# main.net
KiCad netlist of a schematic drawn in EAGLE
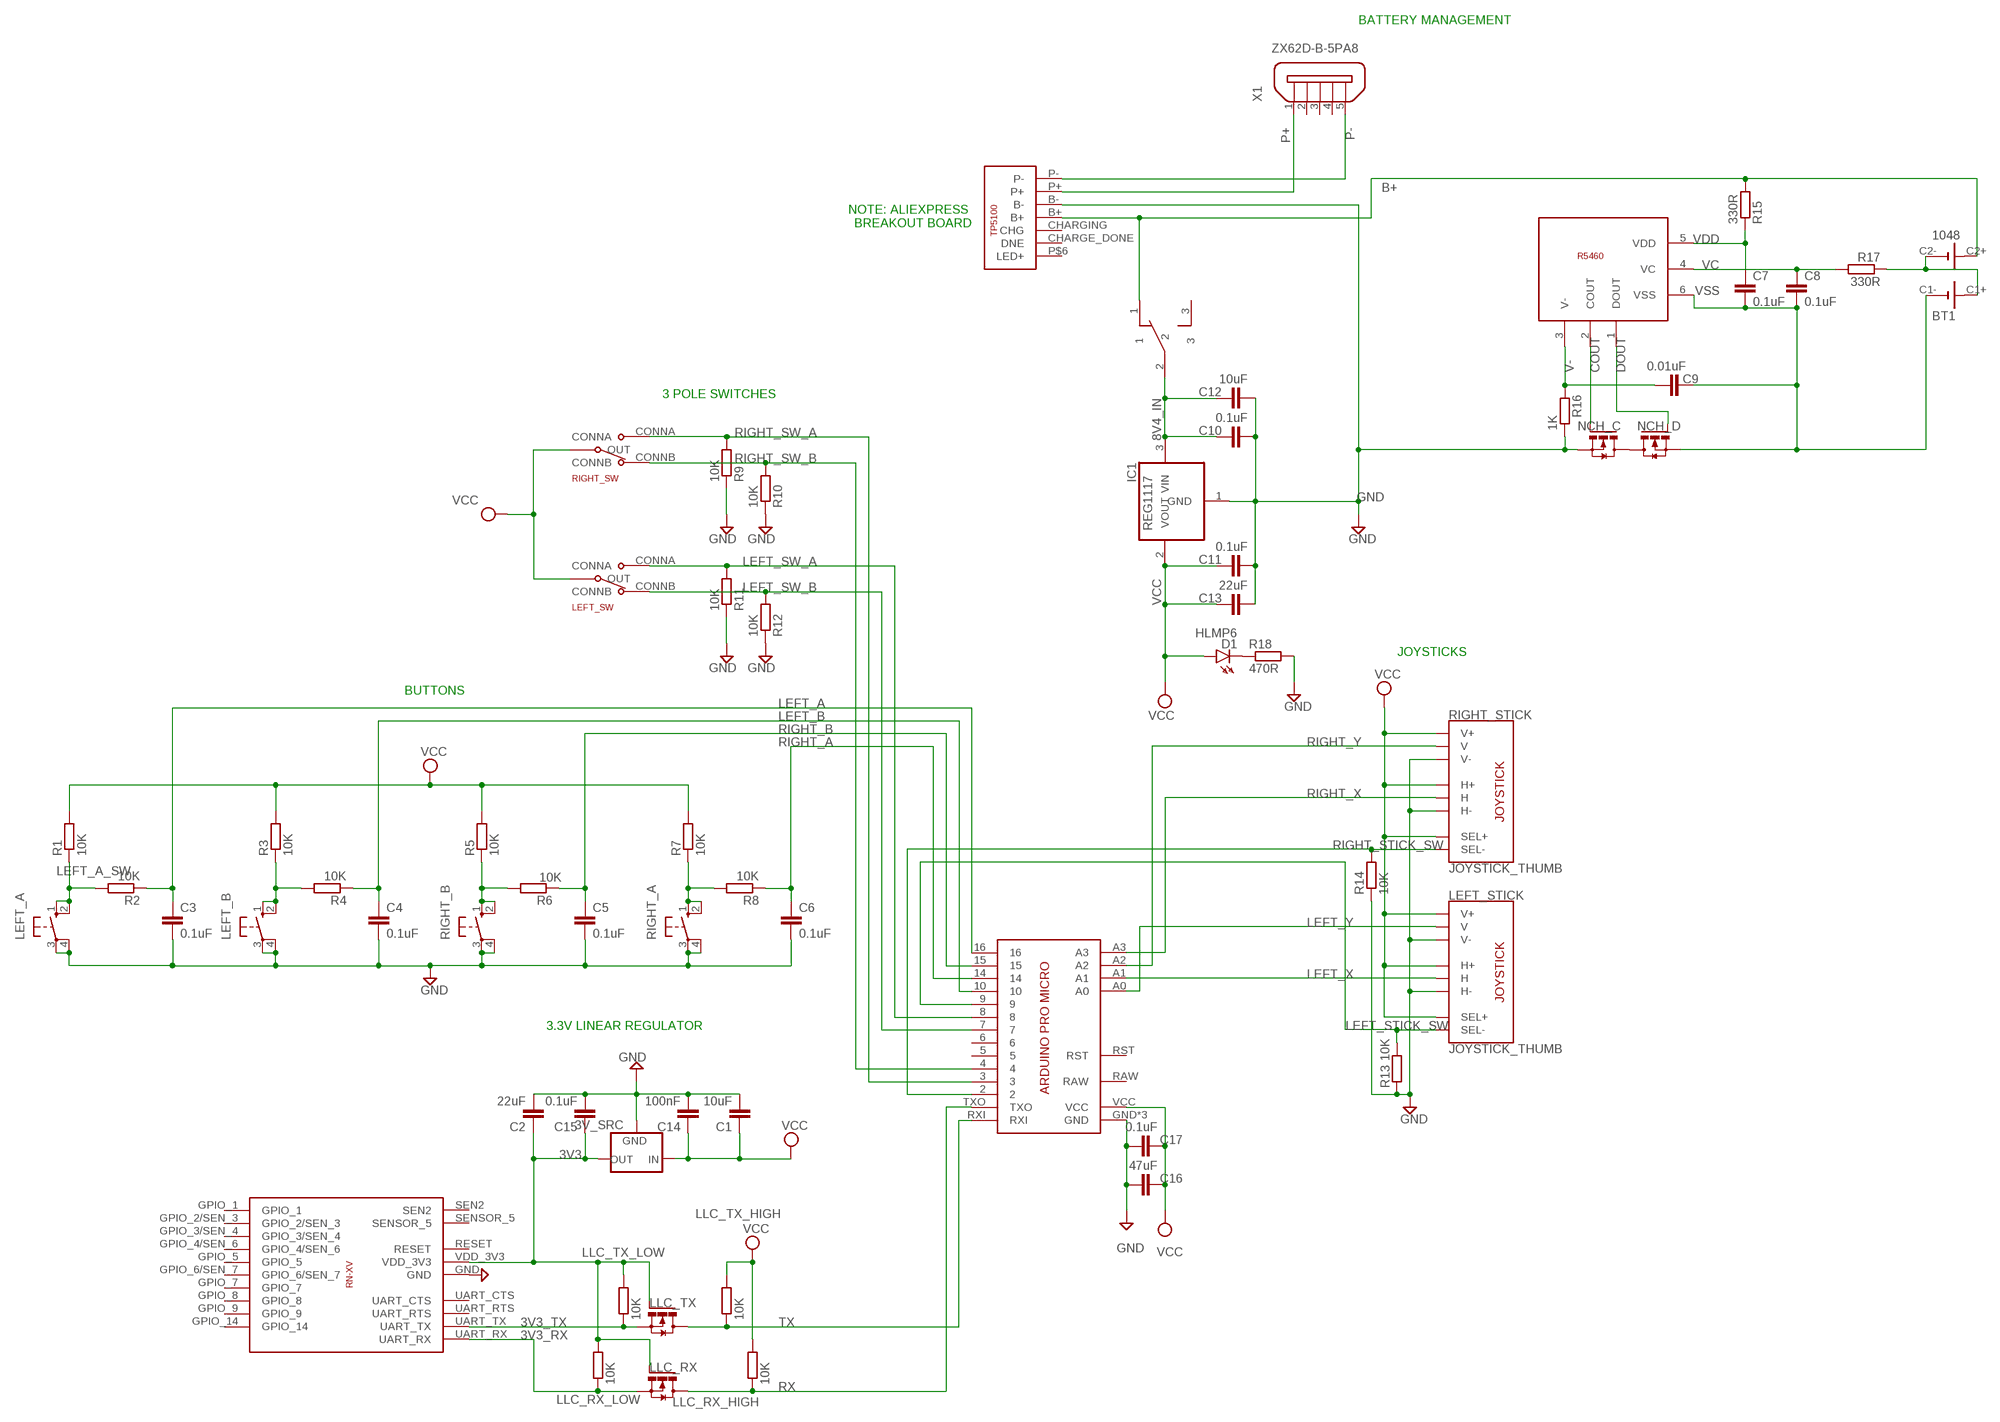
[diagram p0: schematic, sheet 1]

(export (version "E")
  (design (tool "Eeschema 10.0.6"))
  (components
    (comp (ref "3V_SRC")
      (value "V_REG_LD1117VXXLD1117-SMD")
      (footprint "eagle-import:SOT223")
      (libsource (lib "eagle-import") (part "V_REG_LD1117VXXLD1117-SMD"))
    )
    (comp (ref "BT1")
      (value "1048")
      (footprint "eagle-import:BAT_1048")
      (fields (field (name "MF") "Adafruit Industries"))
      (libsource (lib "eagle-import") (part "1048"))
    )
    (comp (ref "C1")
      (value "10uF")
      (footprint "eagle-import:C0805")
      (libsource (lib "eagle-import") (part "C-EUC0805"))
    )
    (comp (ref "C2")
      (value "22uF")
      (footprint "eagle-import:C0805")
      (libsource (lib "eagle-import") (part "C-EUC0805"))
    )
    (comp (ref "C3")
      (value "0.1uF")
      (footprint "eagle-import:0603")
      (libsource (lib "eagle-import") (part "0.1UF-0603-25V-5%"))
    )
    (comp (ref "C4")
      (value "0.1uF")
      (footprint "eagle-import:0603")
      (libsource (lib "eagle-import") (part "0.1UF-0603-25V-5%"))
    )
    (comp (ref "C5")
      (value "0.1uF")
      (footprint "eagle-import:0603")
      (libsource (lib "eagle-import") (part "0.1UF-0603-25V-5%"))
    )
    (comp (ref "C6")
      (value "0.1uF")
      (footprint "eagle-import:0603")
      (libsource (lib "eagle-import") (part "0.1UF-0603-25V-5%"))
    )
    (comp (ref "C7")
      (value "0.1uF")
      (footprint "eagle-import:0603")
      (libsource (lib "eagle-import") (part "0.1UF-0603-25V-(+80/-20%)"))
    )
    (comp (ref "C8")
      (value "0.1uF")
      (footprint "eagle-import:0603")
      (libsource (lib "eagle-import") (part "0.1UF-0603-25V-(+80/-20%)"))
    )
    (comp (ref "C9")
      (value "0.01uF")
      (footprint "eagle-import:0603")
      (libsource (lib "eagle-import") (part "0.1UF-0603-25V-(+80/-20%)"))
    )
    (comp (ref "C10")
      (value "0.1uF")
      (footprint "eagle-import:C0805")
      (libsource (lib "eagle-import") (part "C-EUC0805"))
    )
    (comp (ref "C11")
      (value "0.1uF")
      (footprint "eagle-import:C0805")
      (libsource (lib "eagle-import") (part "C-EUC0805"))
    )
    (comp (ref "C12")
      (value "10uF")
      (footprint "eagle-import:C0805")
      (libsource (lib "eagle-import") (part "C-EUC0805"))
    )
    (comp (ref "C13")
      (value "22uF")
      (footprint "eagle-import:C0805")
      (libsource (lib "eagle-import") (part "C-EUC0805"))
    )
    (comp (ref "C14")
      (value "100nF")
      (footprint "eagle-import:C0805")
      (libsource (lib "eagle-import") (part "C-EUC0805"))
    )
    (comp (ref "C15")
      (value "0.1uF")
      (footprint "eagle-import:C0805")
      (libsource (lib "eagle-import") (part "C-EUC0805"))
    )
    (comp (ref "C16")
      (value "47uF")
      (footprint "eagle-import:C0805")
      (libsource (lib "eagle-import") (part "C-EUC0805"))
    )
    (comp (ref "C17")
      (value "0.1uF")
      (footprint "eagle-import:C0805")
      (libsource (lib "eagle-import") (part "C-EUC0805"))
    )
    (comp (ref "D1")
      (value "HLMP6")
      (footprint "eagle-import:HLMP6")
      (fields (field (name "MF") "AGILENT TECHNOLOGIES") (field (name "MPN") "HLMP-6500"))
      (libsource (lib "eagle-import") (part "HLMP6"))
    )
    (comp (ref "IC1")
      (value "REG1117")
      (footprint "eagle-import:SOT223")
      (libsource (lib "eagle-import") (part "REG1117"))
    )
    (comp (ref "LEFT_A")
      (value "10-XX")
      (footprint "eagle-import:B3F-10XX")
      (fields (field (name "MPN") "B3F-1000"))
      (libsource (lib "eagle-import") (part "10-XX"))
    )
    (comp (ref "LEFT_B")
      (value "10-XX")
      (footprint "eagle-import:B3F-10XX")
      (fields (field (name "MPN") "B3F-1000"))
      (libsource (lib "eagle-import") (part "10-XX"))
    )
    (comp (ref "LEFT_STICK")
      (value "JOYSTICK_THUMB")
      (footprint "eagle-import:JOYSTICK")
      (libsource (lib "eagle-import") (part "JOYSTICK_THUMB"))
    )
    (comp (ref "LEFT_SW")
      (value "2_POLE_SWITCH")
      (footprint "eagle-import:2_POLE_SWITCH")
      (libsource (lib "eagle-import") (part "2_POLE_SWITCH"))
    )
    (comp (ref "LLC_RX")
      (value "2N7002,215")
      (footprint "eagle-import:SOT23-3")
      (fields
        (field (name "DIGIKEY_PART_NUMBER") "1727-2764-1-ND")
        (field (name "MANUFACTURER") "Nexperia USA Inc.")
        (field (name "CREATED_BY") "PCBLayout.com")
      )
      (libsource (lib "eagle-import") (part "2N7002,215"))
    )
    (comp (ref "LLC_RX_HIGH")
      (value "10K")
      (footprint "eagle-import:R0805")
      (libsource (lib "eagle-import") (part "R"))
    )
    (comp (ref "LLC_RX_LOW")
      (value "10K")
      (footprint "eagle-import:R0805")
      (libsource (lib "eagle-import") (part "R"))
    )
    (comp (ref "LLC_TX")
      (value "2N7002,215")
      (footprint "eagle-import:SOT23-3")
      (fields
        (field (name "DIGIKEY_PART_NUMBER") "1727-2764-1-ND")
        (field (name "MANUFACTURER") "Nexperia USA Inc.")
        (field (name "CREATED_BY") "PCBLayout.com")
      )
      (libsource (lib "eagle-import") (part "2N7002,215"))
    )
    (comp (ref "LLC_TX_HIGH")
      (value "10K")
      (footprint "eagle-import:R0805")
      (libsource (lib "eagle-import") (part "R"))
    )
    (comp (ref "LLC_TX_LOW")
      (value "10K")
      (footprint "eagle-import:R0805")
      (libsource (lib "eagle-import") (part "R"))
    )
    (comp (ref "NCH_C")
      (value "FQD13N06LTM")
      (footprint "eagle-import:DPAK4")
      (fields
        (field (name "DIGIKEY_PART_NUMBER") "FQD13N06LTMCT-ND")
        (field (name "MANUFACTURER") "ON Semiconductor")
        (field (name "CREATED_BY") "PCBLayout.com")
      )
      (libsource (lib "eagle-import") (part "FQD13N06LTM"))
    )
    (comp (ref "NCH_D")
      (value "FQD13N06LTM")
      (footprint "eagle-import:DPAK4")
      (fields
        (field (name "DIGIKEY_PART_NUMBER") "FQD13N06LTMCT-ND")
        (field (name "MANUFACTURER") "ON Semiconductor")
        (field (name "CREATED_BY") "PCBLayout.com")
      )
      (libsource (lib "eagle-import") (part "FQD13N06LTM"))
    )
    (comp (ref "R1")
      (value "10K")
      (footprint "eagle-import:R0805")
      (libsource (lib "eagle-import") (part "R"))
    )
    (comp (ref "R2")
      (value "10K")
      (footprint "eagle-import:R0805")
      (libsource (lib "eagle-import") (part "R"))
    )
    (comp (ref "R3")
      (value "10K")
      (footprint "eagle-import:R0805")
      (libsource (lib "eagle-import") (part "R"))
    )
    (comp (ref "R4")
      (value "10K")
      (footprint "eagle-import:R0805")
      (libsource (lib "eagle-import") (part "R"))
    )
    (comp (ref "R5")
      (value "10K")
      (footprint "eagle-import:R0805")
      (libsource (lib "eagle-import") (part "R"))
    )
    (comp (ref "R6")
      (value "10K")
      (footprint "eagle-import:R0805")
      (libsource (lib "eagle-import") (part "R"))
    )
    (comp (ref "R7")
      (value "10K")
      (footprint "eagle-import:R0805")
      (libsource (lib "eagle-import") (part "R"))
    )
    (comp (ref "R8")
      (value "10K")
      (footprint "eagle-import:R0805")
      (libsource (lib "eagle-import") (part "R"))
    )
    (comp (ref "R9")
      (value "10K")
      (footprint "eagle-import:R0805")
      (libsource (lib "eagle-import") (part "R"))
    )
    (comp (ref "R10")
      (value "10K")
      (footprint "eagle-import:R0805")
      (libsource (lib "eagle-import") (part "R"))
    )
    (comp (ref "R11")
      (value "10K")
      (footprint "eagle-import:R0805")
      (libsource (lib "eagle-import") (part "R"))
    )
    (comp (ref "R12")
      (value "10K")
      (footprint "eagle-import:R0805")
      (libsource (lib "eagle-import") (part "R"))
    )
    (comp (ref "R13")
      (value "10K")
      (footprint "eagle-import:R0805")
      (libsource (lib "eagle-import") (part "R"))
    )
    (comp (ref "R14")
      (value "10K")
      (footprint "eagle-import:R0805")
      (libsource (lib "eagle-import") (part "R"))
    )
    (comp (ref "R15")
      (value "330R")
      (footprint "eagle-import:R0805")
      (libsource (lib "eagle-import") (part "R"))
    )
    (comp (ref "R16")
      (value "1K")
      (footprint "eagle-import:R0805")
      (libsource (lib "eagle-import") (part "R"))
    )
    (comp (ref "R17")
      (value "330R")
      (footprint "eagle-import:R0805")
      (libsource (lib "eagle-import") (part "R"))
    )
    (comp (ref "R18")
      (value "470R")
      (footprint "eagle-import:R0805")
      (libsource (lib "eagle-import") (part "R"))
    )
    (comp (ref "R5460")
      (value "R5460")
      (footprint "eagle-import:SOT-23-6")
      (libsource (lib "eagle-import") (part "R5460"))
    )
    (comp (ref "RIGHT_A")
      (value "10-XX")
      (footprint "eagle-import:B3F-10XX")
      (fields (field (name "MPN") "B3F-1000"))
      (libsource (lib "eagle-import") (part "10-XX"))
    )
    (comp (ref "RIGHT_B")
      (value "10-XX")
      (footprint "eagle-import:B3F-10XX")
      (fields (field (name "MPN") "B3F-1000"))
      (libsource (lib "eagle-import") (part "10-XX"))
    )
    (comp (ref "RIGHT_STICK")
      (value "JOYSTICK_THUMB")
      (footprint "eagle-import:JOYSTICK")
      (libsource (lib "eagle-import") (part "JOYSTICK_THUMB"))
    )
    (comp (ref "RIGHT_SW")
      (value "2_POLE_SWITCH")
      (footprint "eagle-import:2_POLE_SWITCH")
      (libsource (lib "eagle-import") (part "2_POLE_SWITCH"))
    )
    (comp (ref "U$1")
      (value "ARDUINO_PRO_MICRO")
      (footprint "eagle-import:ARDUINO_PRO_MICRO")
      (libsource (lib "eagle-import") (part "ARDUINO_PRO_MICRO"))
    )
    (comp (ref "U$2")
      (value "RN-XV")
      (footprint "eagle-import:RN-XV")
      (libsource (lib "eagle-import") (part "RN-XV"))
    )
    (comp (ref "U$4")
      (value "TP5100_MODULE")
      (footprint "eagle-import:TP5100_MODULE")
      (libsource (lib "eagle-import") (part "TP5100_MODULE"))
    )
    (comp (ref "U$6")
      (value "EG1201")
      (footprint "eagle-import:EG1201")
      (libsource (lib "eagle-import") (part "EG1201"))
    )
    (comp (ref "X1")
      (value "ZX62D-B-5PA8")
      (footprint "eagle-import:ZX62D-B-5PA8")
      (fields (field (name "MF") "Hirose"))
      (libsource (lib "eagle-import") (part "ZX62D-B-5PA8"))
    )
  )
  (nets
    (net (code "1") (name "/3V3") (class "Default")
      (node (ref "3V_SRC") (pin "2") (pinfunction "OUT_2") (pintype "passive"))
      (node (ref "C15") (pin "1") (pinfunction "1_1") (pintype "passive"))
      (node (ref "C2") (pin "1") (pinfunction "1_1") (pintype "passive"))
      (node (ref "LLC_RX") (pin "1") (pinfunction "G_1") (pintype "passive"))
      (node (ref "LLC_RX_LOW") (pin "2") (pinfunction "2_2") (pintype "passive"))
      (node (ref "LLC_TX") (pin "1") (pinfunction "G_1") (pintype "passive"))
      (node (ref "LLC_TX_LOW") (pin "2") (pinfunction "2_2") (pintype "passive"))
      (node (ref "U$2") (pin "VDD_3V3") (pinfunction "VDD_3V3_VDD_3V3") (pintype "bidirectional"))
    )
    (net (code "2") (name "/3V3_RX") (class "Default")
      (node (ref "LLC_RX") (pin "2") (pinfunction "S_2") (pintype "passive"))
      (node (ref "LLC_RX_LOW") (pin "1") (pinfunction "1_1") (pintype "passive"))
      (node (ref "U$2") (pin "UART_RX") (pinfunction "UART_RX_UART_RX") (pintype "bidirectional"))
    )
    (net (code "3") (name "/3V3_TX") (class "Default")
      (node (ref "LLC_TX") (pin "2") (pinfunction "S_2") (pintype "passive"))
      (node (ref "LLC_TX_LOW") (pin "1") (pinfunction "1_1") (pintype "passive"))
      (node (ref "U$2") (pin "UART_TX") (pinfunction "UART_TX_UART_TX") (pintype "bidirectional"))
    )
    (net (code "4") (name "/8V4_IN") (class "Default")
      (node (ref "C10") (pin "1") (pinfunction "1_1") (pintype "passive"))
      (node (ref "C12") (pin "1") (pinfunction "1_1") (pintype "passive"))
      (node (ref "IC1") (pin "3") (pinfunction "VIN_3") (pintype "input"))
      (node (ref "U$6") (pin "2") (pinfunction "2_2") (pintype "bidirectional"))
    )
    (net (code "5") (name "/B+") (class "Default")
      (node (ref "BT1") (pin "C2+") (pinfunction "C2+_C2+") (pintype "passive"))
      (node (ref "R15") (pin "2") (pinfunction "2_2") (pintype "passive"))
      (node (ref "U$4") (pin "B+") (pinfunction "B+_B+") (pintype "bidirectional"))
      (node (ref "U$6") (pin "1") (pinfunction "1_1") (pintype "bidirectional"))
    )
    (net (code "6") (name "/COUT") (class "Default")
      (node (ref "NCH_C") (pin "1") (pinfunction "G_1") (pintype "passive"))
      (node (ref "R5460") (pin "2") (pinfunction "COUT_2") (pintype "bidirectional"))
    )
    (net (code "7") (name "/DOUT") (class "Default")
      (node (ref "NCH_D") (pin "1") (pinfunction "G_1") (pintype "passive"))
      (node (ref "R5460") (pin "1") (pinfunction "DOUT_1") (pintype "bidirectional"))
    )
    (net (code "8") (name "/LEFT_A") (class "Default")
      (node (ref "C3") (pin "1") (pinfunction "1_1") (pintype "passive"))
      (node (ref "R2") (pin "1") (pinfunction "1_1") (pintype "passive"))
      (node (ref "U$1") (pin "16") (pinfunction "16_16") (pintype "bidirectional"))
    )
    (net (code "9") (name "/LEFT_A_SW") (class "Default")
      (node (ref "LEFT_A") (pin "1") (pinfunction "S_1") (pintype "passive"))
      (node (ref "LEFT_A") (pin "2") (pinfunction "S1_2") (pintype "passive"))
      (node (ref "R1") (pin "1") (pinfunction "1_1") (pintype "passive"))
      (node (ref "R2") (pin "2") (pinfunction "2_2") (pintype "passive"))
    )
    (net (code "10") (name "/LEFT_B") (class "Default")
      (node (ref "C4") (pin "1") (pinfunction "1_1") (pintype "passive"))
      (node (ref "R4") (pin "1") (pinfunction "1_1") (pintype "passive"))
      (node (ref "U$1") (pin "10") (pinfunction "10_10") (pintype "bidirectional"))
    )
    (net (code "11") (name "/LEFT_STICK_SW") (class "Default")
      (node (ref "LEFT_STICK") (pin "B2A") (pinfunction "SEL-_B2A") (pintype "bidirectional"))
      (node (ref "R13") (pin "2") (pinfunction "2_2") (pintype "passive"))
      (node (ref "U$1") (pin "9") (pinfunction "9_9") (pintype "bidirectional"))
    )
    (net (code "12") (name "/LEFT_SW_A") (class "Default")
      (node (ref "LEFT_SW") (pin "CONNA") (pinfunction "CONNA_CONNA") (pintype "bidirectional"))
      (node (ref "R11") (pin "2") (pinfunction "2_2") (pintype "passive"))
      (node (ref "U$1") (pin "8") (pinfunction "8_8") (pintype "bidirectional"))
    )
    (net (code "13") (name "/LEFT_SW_B") (class "Default")
      (node (ref "LEFT_SW") (pin "CONNB") (pinfunction "CONNB_CONNB") (pintype "bidirectional"))
      (node (ref "R12") (pin "2") (pinfunction "2_2") (pintype "passive"))
      (node (ref "U$1") (pin "7") (pinfunction "7_7") (pintype "bidirectional"))
    )
    (net (code "14") (name "/LEFT_X") (class "Default")
      (node (ref "LEFT_STICK") (pin "H2") (pinfunction "H_H2") (pintype "bidirectional"))
      (node (ref "U$1") (pin "A1") (pinfunction "A1_A1") (pintype "bidirectional"))
    )
    (net (code "15") (name "/LEFT_Y") (class "Default")
      (node (ref "LEFT_STICK") (pin "V2") (pinfunction "V_V2") (pintype "bidirectional"))
      (node (ref "U$1") (pin "A0") (pinfunction "A0_A0") (pintype "bidirectional"))
    )
    (net (code "16") (name "/P+") (class "Default")
      (node (ref "U$4") (pin "P+") (pinfunction "P+_P+") (pintype "bidirectional"))
      (node (ref "X1") (pin "1") (pinfunction "1_1") (pintype "passive"))
    )
    (net (code "17") (name "/P-") (class "Default")
      (node (ref "U$4") (pin "P-") (pinfunction "P-_P-") (pintype "bidirectional"))
      (node (ref "X1") (pin "5") (pinfunction "5_5") (pintype "passive"))
    )
    (net (code "18") (name "/RIGHT_A") (class "Default")
      (node (ref "C6") (pin "1") (pinfunction "1_1") (pintype "passive"))
      (node (ref "R8") (pin "1") (pinfunction "1_1") (pintype "passive"))
      (node (ref "U$1") (pin "14") (pinfunction "14_14") (pintype "bidirectional"))
    )
    (net (code "19") (name "/RIGHT_B") (class "Default")
      (node (ref "C5") (pin "1") (pinfunction "1_1") (pintype "passive"))
      (node (ref "R6") (pin "1") (pinfunction "1_1") (pintype "passive"))
      (node (ref "U$1") (pin "15") (pinfunction "15_15") (pintype "bidirectional"))
    )
    (net (code "20") (name "/RIGHT_STICK_SW") (class "Default")
      (node (ref "R14") (pin "2") (pinfunction "2_2") (pintype "passive"))
      (node (ref "RIGHT_STICK") (pin "B2A") (pinfunction "SEL-_B2A") (pintype "bidirectional"))
      (node (ref "U$1") (pin "2") (pinfunction "2_2") (pintype "bidirectional"))
    )
    (net (code "21") (name "/RIGHT_SW_A") (class "Default")
      (node (ref "R9") (pin "2") (pinfunction "2_2") (pintype "passive"))
      (node (ref "RIGHT_SW") (pin "CONNA") (pinfunction "CONNA_CONNA") (pintype "bidirectional"))
      (node (ref "U$1") (pin "3") (pinfunction "3_3") (pintype "bidirectional"))
    )
    (net (code "22") (name "/RIGHT_SW_B") (class "Default")
      (node (ref "R10") (pin "2") (pinfunction "2_2") (pintype "passive"))
      (node (ref "RIGHT_SW") (pin "CONNB") (pinfunction "CONNB_CONNB") (pintype "bidirectional"))
      (node (ref "U$1") (pin "4") (pinfunction "4_4") (pintype "bidirectional"))
    )
    (net (code "23") (name "/RIGHT_X") (class "Default")
      (node (ref "RIGHT_STICK") (pin "H2") (pinfunction "H_H2") (pintype "bidirectional"))
      (node (ref "U$1") (pin "A3") (pinfunction "A3_A3") (pintype "bidirectional"))
    )
    (net (code "24") (name "/RIGHT_Y") (class "Default")
      (node (ref "RIGHT_STICK") (pin "V2") (pinfunction "V_V2") (pintype "bidirectional"))
      (node (ref "U$1") (pin "A2") (pinfunction "A2_A2") (pintype "bidirectional"))
    )
    (net (code "25") (name "/RX") (class "Default")
      (node (ref "LLC_RX") (pin "3") (pinfunction "D_3") (pintype "passive"))
      (node (ref "LLC_RX_HIGH") (pin "1") (pinfunction "1_1") (pintype "passive"))
      (node (ref "U$1") (pin "TXO") (pinfunction "TXO_TXO") (pintype "bidirectional"))
    )
    (net (code "26") (name "/TX") (class "Default")
      (node (ref "LLC_TX") (pin "3") (pinfunction "D_3") (pintype "passive"))
      (node (ref "LLC_TX_HIGH") (pin "1") (pinfunction "1_1") (pintype "passive"))
      (node (ref "U$1") (pin "RXI") (pinfunction "RXI_RXI") (pintype "bidirectional"))
    )
    (net (code "27") (name "/V-") (class "Default")
      (node (ref "C9") (pin "1") (pinfunction "1_1") (pintype "passive"))
      (node (ref "R16") (pin "2") (pinfunction "2_2") (pintype "passive"))
      (node (ref "R5460") (pin "3") (pinfunction "V-_3") (pintype "bidirectional"))
    )
    (net (code "28") (name "/VC") (class "Default")
      (node (ref "C8") (pin "1") (pinfunction "1_1") (pintype "passive"))
      (node (ref "R17") (pin "2") (pinfunction "2_2") (pintype "passive"))
      (node (ref "R5460") (pin "4") (pinfunction "VC_4") (pintype "bidirectional"))
    )
    (net (code "29") (name "/VDD") (class "Default")
      (node (ref "C7") (pin "1") (pinfunction "1_1") (pintype "passive"))
      (node (ref "R15") (pin "1") (pinfunction "1_1") (pintype "passive"))
      (node (ref "R5460") (pin "5") (pinfunction "VDD_5") (pintype "bidirectional"))
    )
    (net (code "30") (name "/VSS") (class "Default")
      (node (ref "BT1") (pin "C1-") (pinfunction "C1-_C1-") (pintype "passive"))
      (node (ref "C7") (pin "2") (pinfunction "2_2") (pintype "passive"))
      (node (ref "C8") (pin "2") (pinfunction "2_2") (pintype "passive"))
      (node (ref "C9") (pin "2") (pinfunction "2_2") (pintype "passive"))
      (node (ref "NCH_D") (pin "3") (pinfunction "S_3") (pintype "passive"))
      (node (ref "R5460") (pin "6") (pinfunction "VSS_6") (pintype "bidirectional"))
    )
    (net (code "31") (name "GND") (class "Default")
      (node (ref "3V_SRC") (pin "1") (pinfunction "GND_1") (pintype "input"))
      (node (ref "C1") (pin "2") (pinfunction "2_2") (pintype "passive"))
      (node (ref "C10") (pin "2") (pinfunction "2_2") (pintype "passive"))
      (node (ref "C11") (pin "2") (pinfunction "2_2") (pintype "passive"))
      (node (ref "C12") (pin "2") (pinfunction "2_2") (pintype "passive"))
      (node (ref "C13") (pin "2") (pinfunction "2_2") (pintype "passive"))
      (node (ref "C14") (pin "2") (pinfunction "2_2") (pintype "passive"))
      (node (ref "C15") (pin "2") (pinfunction "2_2") (pintype "passive"))
      (node (ref "C16") (pin "2") (pinfunction "2_2") (pintype "passive"))
      (node (ref "C17") (pin "2") (pinfunction "2_2") (pintype "passive"))
      (node (ref "C2") (pin "2") (pinfunction "2_2") (pintype "passive"))
      (node (ref "C3") (pin "2") (pinfunction "2_2") (pintype "passive"))
      (node (ref "C4") (pin "2") (pinfunction "2_2") (pintype "passive"))
      (node (ref "C5") (pin "2") (pinfunction "2_2") (pintype "passive"))
      (node (ref "C6") (pin "2") (pinfunction "2_2") (pintype "passive"))
      (node (ref "IC1") (pin "1") (pinfunction "GND_1") (pintype "power_in"))
      (node (ref "LEFT_A") (pin "3") (pinfunction "P_3") (pintype "passive"))
      (node (ref "LEFT_A") (pin "4") (pinfunction "P1_4") (pintype "passive"))
      (node (ref "LEFT_B") (pin "3") (pinfunction "P_3") (pintype "passive"))
      (node (ref "LEFT_B") (pin "4") (pinfunction "P1_4") (pintype "passive"))
      (node (ref "LEFT_STICK") (pin "H3") (pinfunction "H-_H3") (pintype "bidirectional"))
      (node (ref "LEFT_STICK") (pin "V3") (pinfunction "V-_V3") (pintype "bidirectional"))
      (node (ref "NCH_C") (pin "3") (pinfunction "S_3") (pintype "passive"))
      (node (ref "R10") (pin "1") (pinfunction "1_1") (pintype "passive"))
      (node (ref "R11") (pin "1") (pinfunction "1_1") (pintype "passive"))
      (node (ref "R12") (pin "1") (pinfunction "1_1") (pintype "passive"))
      (node (ref "R13") (pin "1") (pinfunction "1_1") (pintype "passive"))
      (node (ref "R14") (pin "1") (pinfunction "1_1") (pintype "passive"))
      (node (ref "R16") (pin "1") (pinfunction "1_1") (pintype "passive"))
      (node (ref "R18") (pin "2") (pinfunction "2_2") (pintype "passive"))
      (node (ref "R9") (pin "1") (pinfunction "1_1") (pintype "passive"))
      (node (ref "RIGHT_A") (pin "3") (pinfunction "P_3") (pintype "passive"))
      (node (ref "RIGHT_A") (pin "4") (pinfunction "P1_4") (pintype "passive"))
      (node (ref "RIGHT_B") (pin "3") (pinfunction "P_3") (pintype "passive"))
      (node (ref "RIGHT_B") (pin "4") (pinfunction "P1_4") (pintype "passive"))
      (node (ref "RIGHT_STICK") (pin "H3") (pinfunction "H-_H3") (pintype "bidirectional"))
      (node (ref "RIGHT_STICK") (pin "V3") (pinfunction "V-_V3") (pintype "bidirectional"))
      (node (ref "U$1") (pin "GND") (pinfunction "GND_GND") (pintype "bidirectional"))
      (node (ref "U$1") (pin "GND2") (pinfunction "GND_GND2") (pintype "bidirectional"))
      (node (ref "U$1") (pin "GND3") (pinfunction "GND_GND3") (pintype "bidirectional"))
      (node (ref "U$2") (pin "GND") (pinfunction "GND_GND") (pintype "bidirectional"))
      (node (ref "U$4") (pin "B-") (pinfunction "B-_B-") (pintype "bidirectional"))
    )
    (net (code "32") (name "Net-(BT1-PadC1+)") (class "Default")
      (node (ref "BT1") (pin "C1+") (pinfunction "C1+_C1+") (pintype "passive"))
      (node (ref "BT1") (pin "C2-") (pinfunction "C2-_C2-") (pintype "passive"))
      (node (ref "R17") (pin "1") (pinfunction "1_1") (pintype "passive"))
    )
    (net (code "33") (name "Net-(D1-PadK)") (class "Default")
      (node (ref "D1") (pin "K") (pinfunction "K_K") (pintype "passive"))
      (node (ref "R18") (pin "1") (pinfunction "1_1") (pintype "passive"))
    )
    (net (code "34") (name "Net-(LEFT_B-S)") (class "Default")
      (node (ref "LEFT_B") (pin "1") (pinfunction "S_1") (pintype "passive"))
      (node (ref "LEFT_B") (pin "2") (pinfunction "S1_2") (pintype "passive"))
      (node (ref "R3") (pin "1") (pinfunction "1_1") (pintype "passive"))
      (node (ref "R4") (pin "2") (pinfunction "2_2") (pintype "passive"))
    )
    (net (code "35") (name "Net-(NCH_C-D-Pad2)") (class "Default")
      (node (ref "NCH_C") (pin "2") (pinfunction "D_2") (pintype "passive"))
      (node (ref "NCH_C") (pin "4") (pinfunction "D_4") (pintype "passive"))
      (node (ref "NCH_D") (pin "2") (pinfunction "D_2") (pintype "passive"))
      (node (ref "NCH_D") (pin "4") (pinfunction "D_4") (pintype "passive"))
    )
    (net (code "36") (name "Net-(RIGHT_A-S)") (class "Default")
      (node (ref "R7") (pin "1") (pinfunction "1_1") (pintype "passive"))
      (node (ref "R8") (pin "2") (pinfunction "2_2") (pintype "passive"))
      (node (ref "RIGHT_A") (pin "1") (pinfunction "S_1") (pintype "passive"))
      (node (ref "RIGHT_A") (pin "2") (pinfunction "S1_2") (pintype "passive"))
    )
    (net (code "37") (name "Net-(RIGHT_B-S)") (class "Default")
      (node (ref "R5") (pin "1") (pinfunction "1_1") (pintype "passive"))
      (node (ref "R6") (pin "2") (pinfunction "2_2") (pintype "passive"))
      (node (ref "RIGHT_B") (pin "1") (pinfunction "S_1") (pintype "passive"))
      (node (ref "RIGHT_B") (pin "2") (pinfunction "S1_2") (pintype "passive"))
    )
    (net (code "38") (name "VCC") (class "Default")
      (node (ref "3V_SRC") (pin "3") (pinfunction "IN_3") (pintype "input"))
      (node (ref "C1") (pin "1") (pinfunction "1_1") (pintype "passive"))
      (node (ref "C11") (pin "1") (pinfunction "1_1") (pintype "passive"))
      (node (ref "C13") (pin "1") (pinfunction "1_1") (pintype "passive"))
      (node (ref "C14") (pin "1") (pinfunction "1_1") (pintype "passive"))
      (node (ref "C16") (pin "1") (pinfunction "1_1") (pintype "passive"))
      (node (ref "C17") (pin "1") (pinfunction "1_1") (pintype "passive"))
      (node (ref "D1") (pin "A") (pinfunction "A_A") (pintype "passive"))
      (node (ref "IC1") (pin "2") (pinfunction "VOUT_2") (pintype "output"))
      (node (ref "LEFT_STICK") (pin "B1A") (pinfunction "SEL+_B1A") (pintype "bidirectional"))
      (node (ref "LEFT_STICK") (pin "H1") (pinfunction "H+_H1") (pintype "bidirectional"))
      (node (ref "LEFT_STICK") (pin "V1") (pinfunction "V+_V1") (pintype "bidirectional"))
      (node (ref "LEFT_SW") (pin "OUT") (pinfunction "OUT_OUT") (pintype "bidirectional"))
      (node (ref "LLC_RX_HIGH") (pin "2") (pinfunction "2_2") (pintype "passive"))
      (node (ref "LLC_TX_HIGH") (pin "2") (pinfunction "2_2") (pintype "passive"))
      (node (ref "R1") (pin "2") (pinfunction "2_2") (pintype "passive"))
      (node (ref "R3") (pin "2") (pinfunction "2_2") (pintype "passive"))
      (node (ref "R5") (pin "2") (pinfunction "2_2") (pintype "passive"))
      (node (ref "R7") (pin "2") (pinfunction "2_2") (pintype "passive"))
      (node (ref "RIGHT_STICK") (pin "B1A") (pinfunction "SEL+_B1A") (pintype "bidirectional"))
      (node (ref "RIGHT_STICK") (pin "H1") (pinfunction "H+_H1") (pintype "bidirectional"))
      (node (ref "RIGHT_STICK") (pin "V1") (pinfunction "V+_V1") (pintype "bidirectional"))
      (node (ref "RIGHT_SW") (pin "OUT") (pinfunction "OUT_OUT") (pintype "bidirectional"))
      (node (ref "U$1") (pin "VCC") (pinfunction "VCC_VCC") (pintype "bidirectional"))
    )
    (net (code "39") (name "unconnected-(U$1-Pad5)") (class "Default")
      (node (ref "U$1") (pin "5") (pinfunction "5_5") (pintype "bidirectional"))
    )
    (net (code "40") (name "unconnected-(U$1-Pad6)") (class "Default")
      (node (ref "U$1") (pin "6") (pinfunction "6_6") (pintype "bidirectional"))
    )
    (net (code "41") (name "unconnected-(U$1-PadRAW)") (class "Default")
      (node (ref "U$1") (pin "RAW") (pinfunction "RAW_RAW") (pintype "bidirectional"))
    )
    (net (code "42") (name "unconnected-(U$1-PadRST)") (class "Default")
      (node (ref "U$1") (pin "RST") (pinfunction "RST_RST") (pintype "bidirectional"))
    )
    (net (code "43") (name "unconnected-(U$2-PadGPIO_1)") (class "Default")
      (node (ref "U$2") (pin "GPIO_1") (pinfunction "GPIO_1_GPIO_1") (pintype "bidirectional"))
    )
    (net (code "44") (name "unconnected-(U$2-PadGPIO_2{slash}SEN_3)") (class "Default")
      (node (ref "U$2") (pin "GPIO_2/SEN_3") (pinfunction "GPIO_2/SEN_3_GPIO_2/SEN_3") (pintype "bidirectional"))
    )
    (net (code "45") (name "unconnected-(U$2-PadGPIO_3{slash}SEN_4)") (class "Default")
      (node (ref "U$2") (pin "GPIO_3/SEN_4") (pinfunction "GPIO_3/SEN_4_GPIO_3/SEN_4") (pintype "bidirectional"))
    )
    (net (code "46") (name "unconnected-(U$2-PadGPIO_4{slash}SEN_6)") (class "Default")
      (node (ref "U$2") (pin "GPIO_4/SEN_6") (pinfunction "GPIO_4/SEN_6_GPIO_4/SEN_6") (pintype "bidirectional"))
    )
    (net (code "47") (name "unconnected-(U$2-PadGPIO_5)") (class "Default")
      (node (ref "U$2") (pin "GPIO_5") (pinfunction "GPIO_5_GPIO_5") (pintype "bidirectional"))
    )
    (net (code "48") (name "unconnected-(U$2-PadGPIO_6{slash}SEN_7)") (class "Default")
      (node (ref "U$2") (pin "GPIO_6/SEN_7") (pinfunction "GPIO_6/SEN_7_GPIO_6/SEN_7") (pintype "bidirectional"))
    )
    (net (code "49") (name "unconnected-(U$2-PadGPIO_7)") (class "Default")
      (node (ref "U$2") (pin "GPIO_7") (pinfunction "GPIO_7_GPIO_7") (pintype "bidirectional"))
    )
    (net (code "50") (name "unconnected-(U$2-PadGPIO_8)") (class "Default")
      (node (ref "U$2") (pin "GPIO_8") (pinfunction "GPIO_8_GPIO_8") (pintype "bidirectional"))
    )
    (net (code "51") (name "unconnected-(U$2-PadGPIO_9)") (class "Default")
      (node (ref "U$2") (pin "GPIO_9") (pinfunction "GPIO_9_GPIO_9") (pintype "bidirectional"))
    )
    (net (code "52") (name "unconnected-(U$2-PadGPIO_14)") (class "Default")
      (node (ref "U$2") (pin "GPIO_14") (pinfunction "GPIO_14_GPIO_14") (pintype "bidirectional"))
    )
    (net (code "53") (name "unconnected-(U$2-PadRESET)") (class "Default")
      (node (ref "U$2") (pin "RESET") (pinfunction "RESET_RESET") (pintype "bidirectional"))
    )
    (net (code "54") (name "unconnected-(U$2-PadSEN2)") (class "Default")
      (node (ref "U$2") (pin "SEN2") (pinfunction "SEN2_SEN2") (pintype "bidirectional"))
    )
    (net (code "55") (name "unconnected-(U$2-PadSENSOR_5)") (class "Default")
      (node (ref "U$2") (pin "SENSOR_5") (pinfunction "SENSOR_5_SENSOR_5") (pintype "bidirectional"))
    )
    (net (code "56") (name "unconnected-(U$2-PadUART_CTS)") (class "Default")
      (node (ref "U$2") (pin "UART_CTS") (pinfunction "UART_CTS_UART_CTS") (pintype "bidirectional"))
    )
    (net (code "57") (name "unconnected-(U$2-PadUART_RTS)") (class "Default")
      (node (ref "U$2") (pin "UART_RTS") (pinfunction "UART_RTS_UART_RTS") (pintype "bidirectional"))
    )
    (net (code "58") (name "unconnected-(U$4-CHG-PadCHARGING)") (class "Default")
      (node (ref "U$4") (pin "CHARGING") (pinfunction "CHG_CHARGING") (pintype "bidirectional"))
    )
    (net (code "59") (name "unconnected-(U$4-DNE-PadCHARGE_DONE)") (class "Default")
      (node (ref "U$4") (pin "CHARGE_DONE") (pinfunction "DNE_CHARGE_DONE") (pintype "bidirectional"))
    )
    (net (code "60") (name "unconnected-(U$4-LED+-PadP$6)") (class "Default")
      (node (ref "U$4") (pin "P$6") (pinfunction "LED+_P$6") (pintype "bidirectional"))
    )
    (net (code "61") (name "unconnected-(U$6-Pad3)") (class "Default")
      (node (ref "U$6") (pin "3") (pinfunction "3_3") (pintype "bidirectional"))
    )
    (net (code "62") (name "unconnected-(X1-Pad2)") (class "Default")
      (node (ref "X1") (pin "2") (pinfunction "2_2") (pintype "passive"))
    )
    (net (code "63") (name "unconnected-(X1-Pad3)") (class "Default")
      (node (ref "X1") (pin "3") (pinfunction "3_3") (pintype "passive"))
    )
    (net (code "64") (name "unconnected-(X1-Pad4)") (class "Default")
      (node (ref "X1") (pin "4") (pinfunction "4_4") (pintype "passive"))
    )
  )
)
